# mission_unsleepable.net
KiCad netlist of a schematic drawn in Altium Designer
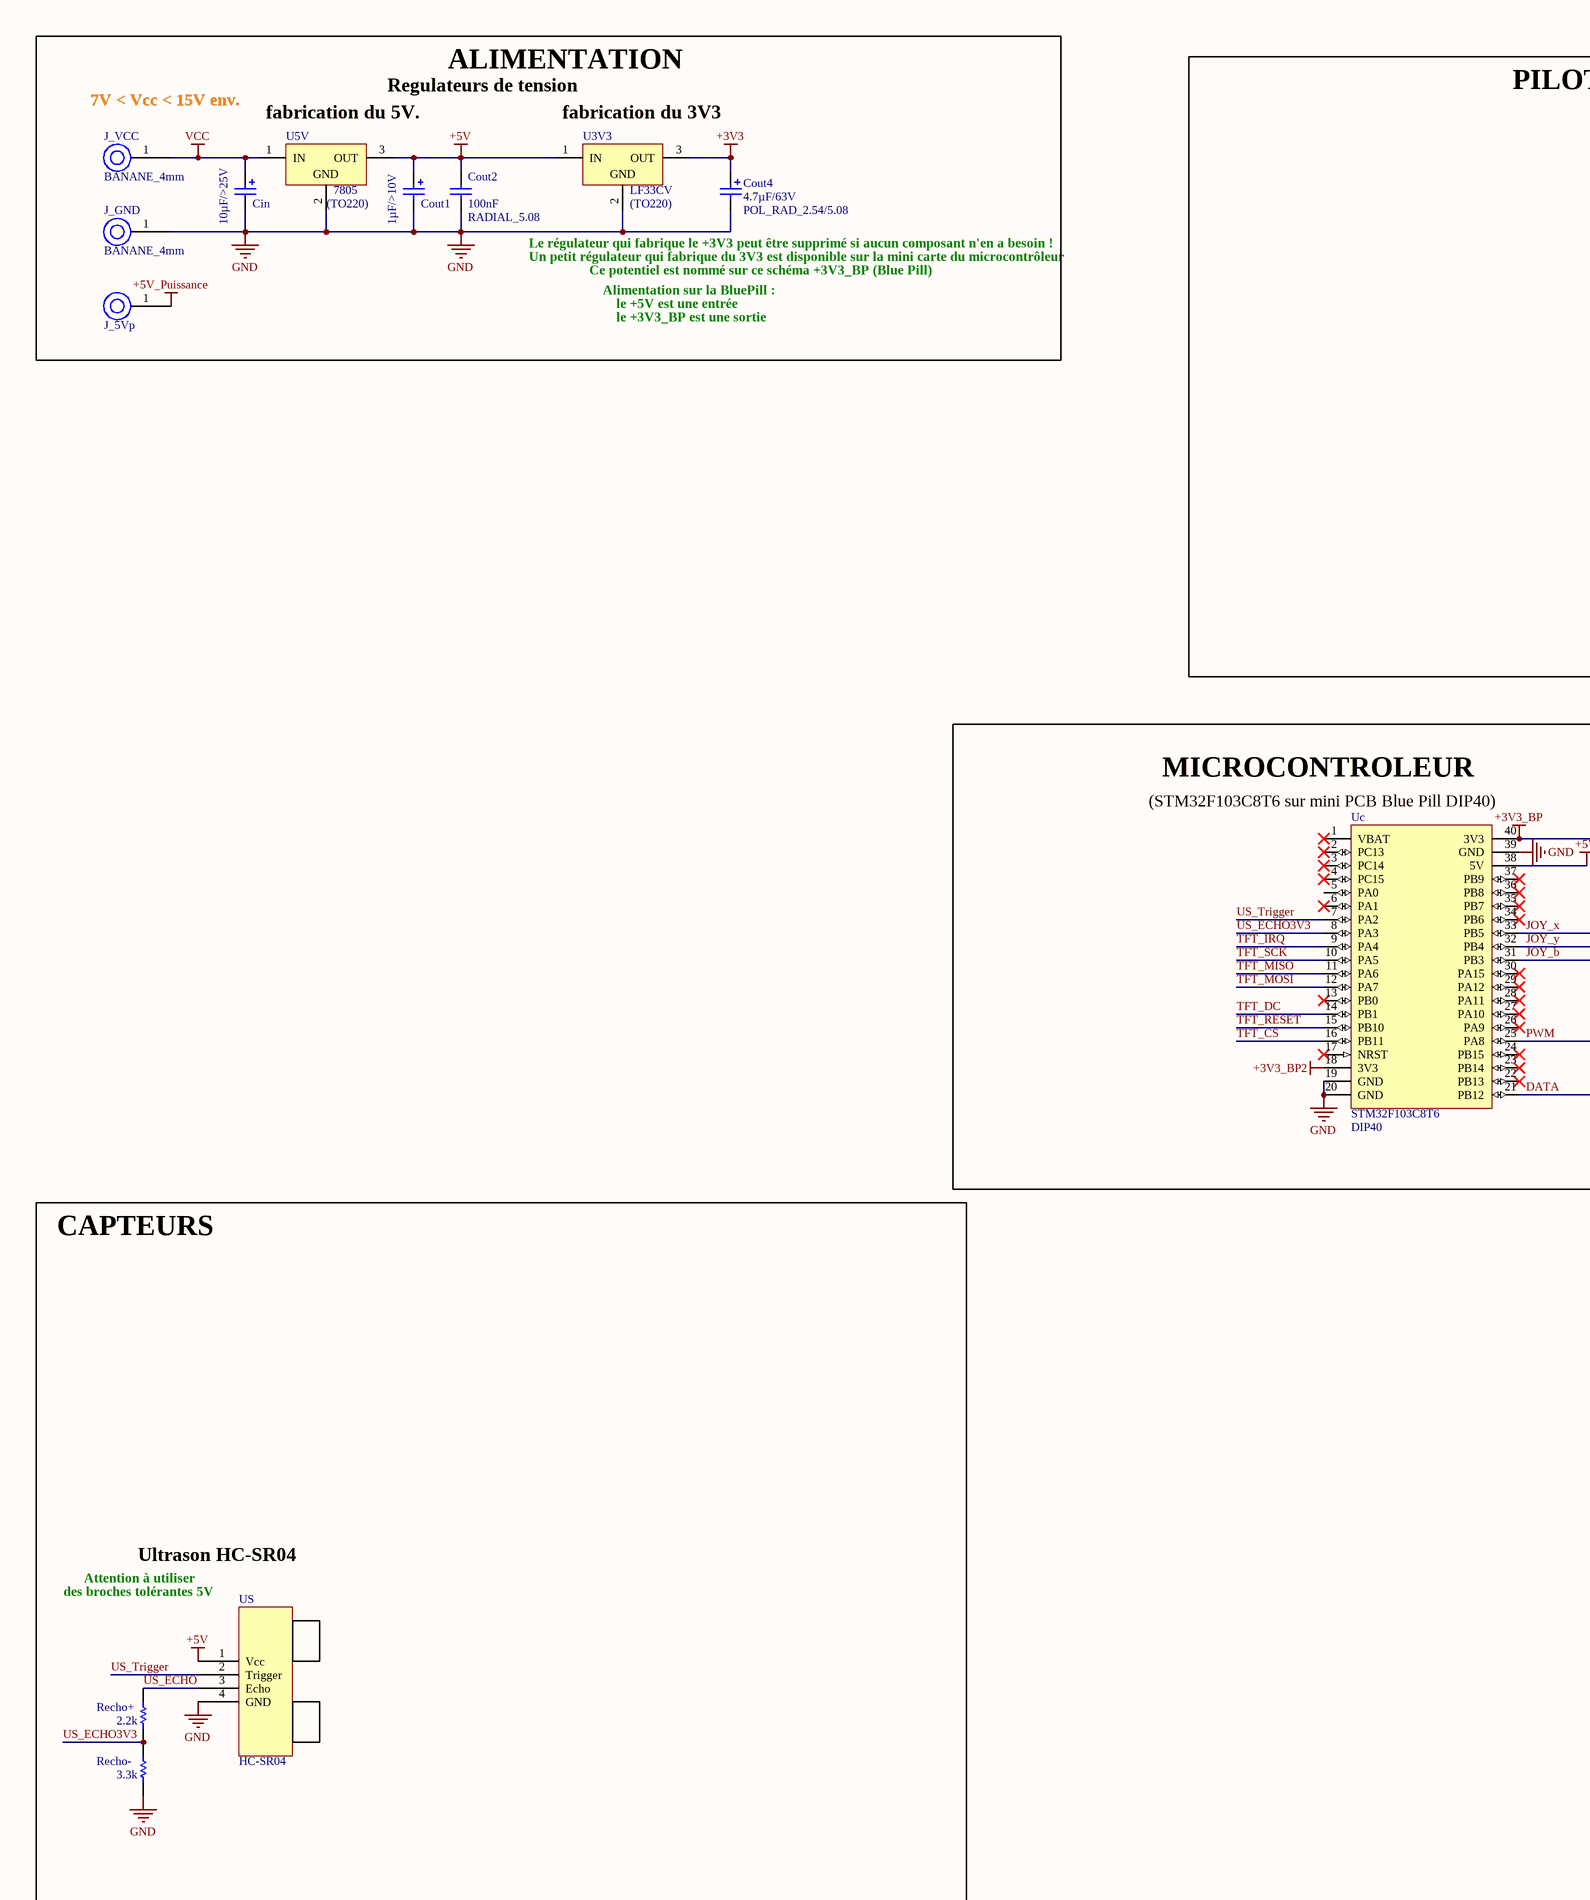
[diagram p0: mission_unsleepable.SchDoc, left]
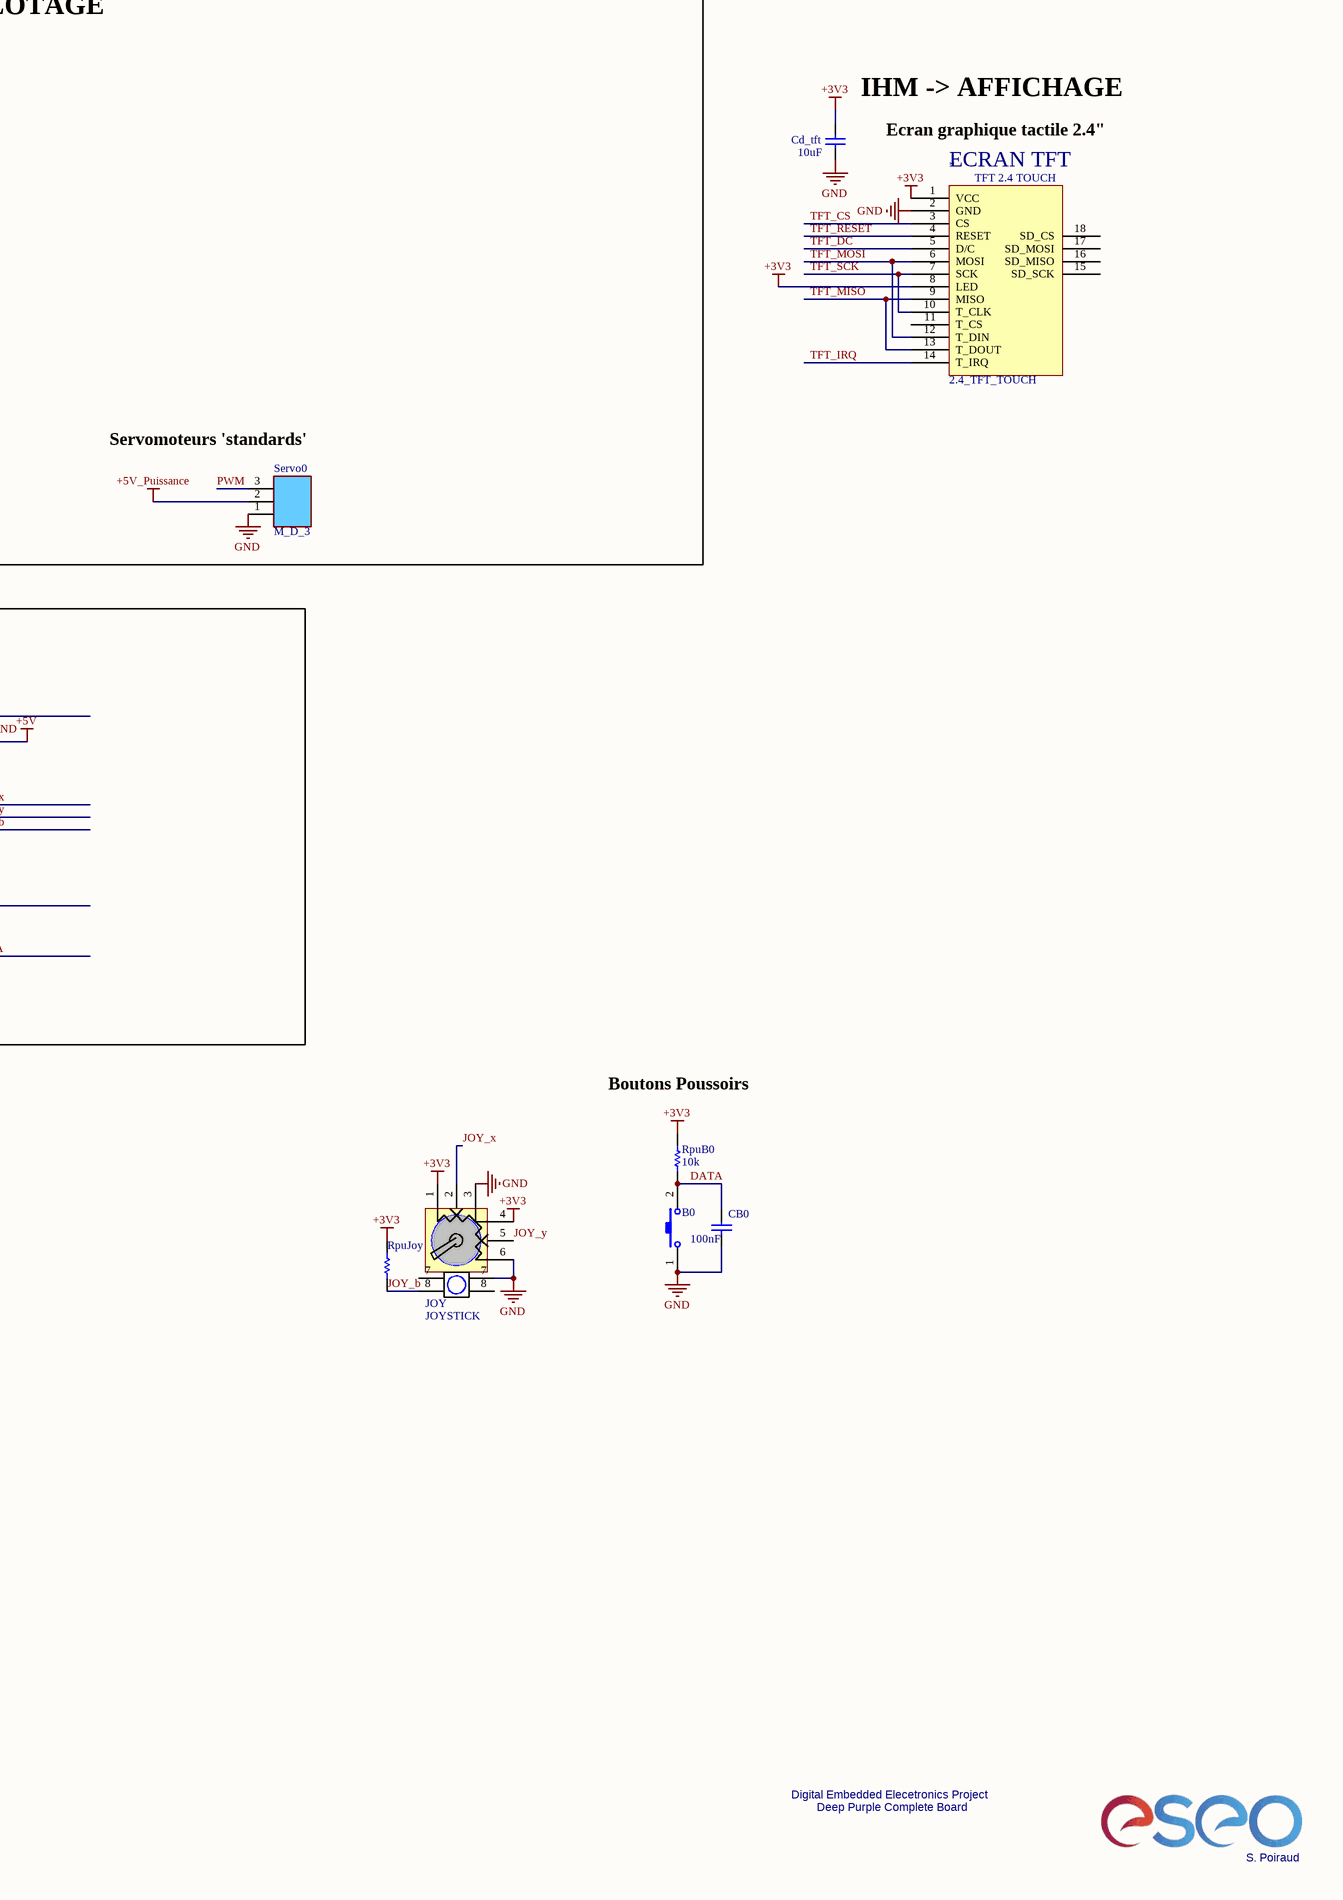
[diagram p1: mission_unsleepable.SchDoc, right]

(export (version "E")
  (design (tool "Eeschema 10.0.6"))
  (components
    (comp (ref "*")
      (value "2.4_TFT_TOUCH")
      (footprint "2.4_TFT_TOUCH")
      (libsource (lib "_ROBOT") (part "2.4_TFT_TOUCH"))
    )
    (comp (ref "B0")
      (value "BOUTON_POUSSOIR_MINIATURE_TRAVERSANT")
      (footprint "BOUTON_POUSSE_PLAT_6x6")
      (description "BOUTON POUSSOIR MINIATURE TRAVERSANT ON/OFF")
      (libsource (lib "commutation") (part "BOUTON_POUSSOIR_MINIATURE_TRAVERSANT"))
    )
    (comp (ref "CB0")
      (value "100nF")
      (footprint "C0805_N")
      (fields (field (name "Comment") "Condensateur 0805"))
      (libsource (lib "composants passifs") (part "CONDENSATEUR_CER_RAD_5.08"))
    )
    (comp (ref "Cd_tft")
      (value "10uF")
      (footprint "CONDENSATEUR_POLARISE_ELECTROLYTIQUE_RADIAL_2.54/5.08")
      (description "Capacitor")
      (fields (field (name "PUBLISHER") "Altium Limited"))
      (libsource (lib "_ROBOT") (part "Condensateur"))
    )
    (comp (ref "Cin")
      (value "10µF/>25V")
      (footprint "CONDENSATEUR_POLARISE_ELECTROLYTIQUE_RADIAL_2.0/5.08")
      (description "CONDENSATEUR POLARISE ELECTROLYTIQUE RADIAL 2.0/5.08")
      (fields (field (name "Comment") "CONDENSATEUR_POL_ELECTROLY_RAD_2.0/5.08"))
      (libsource (lib "composants passifs") (part "CONDENSATEUR_POL_ELECTROLY_RAD_2.0/5.08"))
    )
    (comp (ref "Cout1")
      (value "1µF/>10V")
      (footprint "CONDENSATEUR_POLARISE_ELECTROLYTIQUE_RADIAL_2.0/5.08")
      (description "CONDENSATEUR POLARISE ELECTROLYTIQUE RADIAL 2.0/5.08")
      (fields (field (name "Comment") "CONDENSATEUR_POL_ELECTROLY_RAD_2.0/5.08"))
      (libsource (lib "composants passifs") (part "CONDENSATEUR_POL_ELECTROLY_RAD_2.0/5.08"))
    )
    (comp (ref "Cout2")
      (value "100nF")
      (footprint "CONDENSATEUR_CERAMIQUE_RADIAL_5.08")
      (description "CONDENSATEUR TRAVERSANT CERAMIQUE RADIAL 5.08mm")
      (fields (field (name "TYPE") "RADIAL_5.08") (field (name "Comment") "CONDENSATEUR_CER_RAD_5.08"))
      (libsource (lib "composants passifs") (part "CONDENSATEUR_CER_RAD_5.08"))
    )
    (comp (ref "Cout4")
      (value "4.7µF/63V")
      (footprint "CONDENSATEUR_POLARISE_ELECTROLYTIQUE_RADIAL_2.54/5.08")
      (description "CONDENSATEUR POLARISE ELECTROLYTIQUE RADIAL 2.54/5.08")
      (fields
        (field (name "TYPE") "POL_RAD_2.54/5.08")
        (field (name "Comment") "CONDENSATEUR_POL_ELECTROLY_RAD_2.54/5.08")
      )
      (libsource (lib "composants passifs") (part "CONDENSATEUR_POL_ELECTROLY_RAD_2.54/5.08"))
    )
    (comp (ref "JOY")
      (value "JOYSTICK_MINI_AVEC_SWITCH")
      (footprint "JOYSTICK_MINI - avec Switch")
      (description "JOYSTICK POTENTIOMETRIQUE MINIATURE RKJXK122000D")
      (fields (field (name "TYPE") "JOYSTICK"))
      (libsource (lib "electromecanique") (part "JOYSTICK_MINI_AVEC_SWITCH"))
    )
    (comp (ref "J_5Vp")
      (value "DOUILLE BANANE 4mm")
      (footprint "DOUILLE_BANANE_4mm")
      (description "DOUILLE BANANE 4 mm")
      (libsource (lib "connecteurs") (part "DOUILLE_BANANE_4mm"))
    )
    (comp (ref "J_GND")
      (value "DOUILLE BANANE 4mm")
      (footprint "DOUILLE_BANANE_4mm")
      (description "DOUILLE BANANE 4 mm")
      (fields (field (name "TYPE") "BANANE_4mm"))
      (libsource (lib "connecteurs") (part "DOUILLE_BANANE_4mm"))
    )
    (comp (ref "J_VCC")
      (value "DOUILLE BANANE 4mm")
      (footprint "DOUILLE_BANANE_4mm")
      (description "DOUILLE BANANE 4 mm")
      (fields (field (name "TYPE") "BANANE_4mm"))
      (libsource (lib "connecteurs") (part "DOUILLE_BANANE_4mm"))
    )
    (comp (ref "Recho+")
      (value "2.2k")
      (footprint "R1206_N")
      (description "Resistor")
      (fields (field (name "PUBLISHER") "Altium Limited"))
      (libsource (lib "_ROBOT") (part "Resistor"))
    )
    (comp (ref "Recho-")
      (value "3.3k")
      (footprint "R1206_N")
      (description "Resistor")
      (fields (field (name "PUBLISHER") "Altium Limited"))
      (libsource (lib "_ROBOT") (part "Resistor"))
    )
    (comp (ref "RpuB0")
      (value "10k")
      (footprint "RESISTANCE_CMS_1206")
      (description "RESISTANCE CMS 1206")
      (fields (field (name "Comment") "RESISTANCE_CMS_1206"))
      (libsource (lib "composants passifs") (part "RESISTANCE_CMS_1206"))
    )
    (comp (ref "RpuJoy")
      (value "RESISTANCE_CMS_1206")
      (footprint "RESISTANCE_CMS_1206")
      (description "RESISTANCE CMS 1206")
      (libsource (lib "composants passifs") (part "RESISTANCE_CMS_1206"))
    )
    (comp (ref "Servo0")
      (value "BARRETTE 3 CONTACTS 1 RANGEE MALE DROITE")
      (footprint "BARRETTE_3_M_D")
      (fields (field (name "TYPE") "M_D_3"))
      (libsource (lib "connecteurs") (part "BARRETTE_3 CONTACTS_1 RANGEE_MALE_DROITE"))
    )
    (comp (ref "U3V3")
      (value "REGULATEUR_TO220_78XX")
      (footprint "REGULATEUR_TO220_78XX")
      (description "REGULATEUR DE TENSION POSITIVE 78XX BOITIER TO220")
      (fields (field (name "TYPE") "LF33CV") (field (name "PACKAGE") "(TO220)"))
      (libsource (lib "composants actifs") (part "REGULATEUR_TO220_78XX"))
    )
    (comp (ref "U5V")
      (value "REGULATEUR_TO220_78XX")
      (footprint "REGULATEUR_TO220_78XX")
      (description "REGULATEUR DE TENSION POSITIVE 78XX BOITIER TO220")
      (fields (field (name "TYPE") "7805") (field (name "PACKAGE") "(TO220)"))
      (libsource (lib "composants actifs") (part "REGULATEUR_TO220_78XX"))
    )
    (comp (ref "Uc")
      (value "STM32F103C8T6/PCB_DIP40")
      (footprint "STM32F103C8T6_DIP40")
      (fields (field (name "TYPE") "STM32F103C8T6") (field (name "PACKAGE") "DIP40"))
      (libsource (lib "circuits integres") (part "STM32F103C8T6/PCB_DIP40"))
    )
    (comp (ref "US") (value "HC-SR04") (footprint "HC-SR04") (libsource (lib "DEEP") (part "HC-SR04")))
  )
  (nets
    (net (code "1") (name "+3V3") (class "Default")
      (node (ref "*") (pin "1") (pinfunction "VCC_1") (pintype "passive"))
      (node (ref "*") (pin "8") (pinfunction "LED_8") (pintype "passive"))
      (node (ref "Cd_tft") (pin "1") (pinfunction "1_1") (pintype "passive"))
      (node (ref "Cout4") (pin "1") (pinfunction "1_1") (pintype "passive"))
      (node (ref "JOY") (pin "1") (pintype "passive"))
      (node (ref "JOY") (pin "4") (pintype "passive"))
      (node (ref "RpuB0") (pin "2") (pinfunction "2_2") (pintype "passive"))
      (node (ref "RpuJoy") (pin "2") (pinfunction "2_2") (pintype "passive"))
      (node (ref "U3V3") (pin "3") (pinfunction "OUT_3") (pintype "power_in"))
    )
    (net (code "2") (name "+3V3_BP") (class "Default")
      (node (ref "Uc") (pin "40") (pinfunction "3V3_40") (pintype "power_in"))
    )
    (net (code "3") (name "+3V3_BP2") (class "Default")
      (node (ref "Uc") (pin "18") (pinfunction "3V3_18") (pintype "power_in"))
    )
    (net (code "4") (name "+5V") (class "Default")
      (node (ref "Cout1") (pin "1") (pinfunction "1_1") (pintype "passive"))
      (node (ref "Cout2") (pin "2") (pinfunction "2_2") (pintype "passive"))
      (node (ref "U3V3") (pin "1") (pinfunction "IN_1") (pintype "power_in"))
      (node (ref "U5V") (pin "3") (pinfunction "OUT_3") (pintype "power_in"))
      (node (ref "US") (pin "1") (pinfunction "Vcc_1") (pintype "passive"))
      (node (ref "Uc") (pin "38") (pinfunction "5V_38") (pintype "power_in"))
    )
    (net (code "5") (name "+5V_Puissance") (class "Default")
      (node (ref "J_5Vp") (pin "1") (pinfunction "1_1") (pintype "passive"))
      (node (ref "Servo0") (pin "2") (pinfunction "2_2") (pintype "passive"))
    )
    (net (code "6") (name "/DATA") (class "Default")
      (node (ref "B0") (pin "2") (pinfunction "2_2") (pintype "passive"))
      (node (ref "CB0") (pin "2") (pinfunction "2_2") (pintype "passive"))
      (node (ref "RpuB0") (pin "1") (pinfunction "1_1") (pintype "passive"))
      (node (ref "Uc") (pin "21") (pinfunction "PB12_21") (pintype "bidirectional"))
    )
    (net (code "7") (name "/JOY_b") (class "Default")
      (node (ref "JOY") (pin "8") (pintype "passive"))
      (node (ref "RpuJoy") (pin "1") (pinfunction "1_1") (pintype "passive"))
      (node (ref "Uc") (pin "31") (pinfunction "PB3_31") (pintype "bidirectional"))
    )
    (net (code "8") (name "/JOY_x") (class "Default")
      (node (ref "JOY") (pin "2") (pintype "passive"))
      (node (ref "Uc") (pin "33") (pinfunction "PB5_33") (pintype "bidirectional"))
    )
    (net (code "9") (name "/JOY_y") (class "Default")
      (node (ref "JOY") (pin "5") (pintype "passive"))
      (node (ref "Uc") (pin "32") (pinfunction "PB4_32") (pintype "bidirectional"))
    )
    (net (code "10") (name "/PWM") (class "Default")
      (node (ref "Servo0") (pin "3") (pinfunction "3_3") (pintype "passive"))
      (node (ref "Uc") (pin "25") (pinfunction "PA8_25") (pintype "bidirectional"))
    )
    (net (code "11") (name "/TFT_CS") (class "Default")
      (node (ref "*") (pin "3") (pinfunction "CS_3") (pintype "passive"))
      (node (ref "Uc") (pin "16") (pinfunction "PB11_16") (pintype "bidirectional"))
    )
    (net (code "12") (name "/TFT_DC") (class "Default")
      (node (ref "*") (pin "5") (pinfunction "D/C_5") (pintype "passive"))
      (node (ref "Uc") (pin "14") (pinfunction "PB1_14") (pintype "bidirectional"))
    )
    (net (code "13") (name "/TFT_IRQ") (class "Default")
      (node (ref "*") (pin "14") (pinfunction "T_IRQ_14") (pintype "passive"))
      (node (ref "Uc") (pin "9") (pinfunction "PA4_9") (pintype "bidirectional"))
    )
    (net (code "14") (name "/TFT_MISO") (class "Default")
      (node (ref "*") (pin "13") (pinfunction "T_DOUT_13") (pintype "passive"))
      (node (ref "*") (pin "9") (pinfunction "MISO_9") (pintype "passive"))
      (node (ref "Uc") (pin "11") (pinfunction "PA6_11") (pintype "bidirectional"))
    )
    (net (code "15") (name "/TFT_MOSI") (class "Default")
      (node (ref "*") (pin "12") (pinfunction "T_DIN_12") (pintype "passive"))
      (node (ref "*") (pin "6") (pinfunction "MOSI_6") (pintype "passive"))
      (node (ref "Uc") (pin "12") (pinfunction "PA7_12") (pintype "bidirectional"))
    )
    (net (code "16") (name "/TFT_RESET") (class "Default")
      (node (ref "*") (pin "4") (pinfunction "RESET_4") (pintype "passive"))
      (node (ref "Uc") (pin "15") (pinfunction "PB10_15") (pintype "bidirectional"))
    )
    (net (code "17") (name "/TFT_SCK") (class "Default")
      (node (ref "*") (pin "10") (pinfunction "T_CLK_10") (pintype "passive"))
      (node (ref "*") (pin "7") (pinfunction "SCK_7") (pintype "passive"))
      (node (ref "Uc") (pin "10") (pinfunction "PA5_10") (pintype "bidirectional"))
    )
    (net (code "18") (name "/US_ECHO") (class "Default")
      (node (ref "Recho+") (pin "2") (pinfunction "2_2") (pintype "passive"))
      (node (ref "US") (pin "3") (pinfunction "Echo_3") (pintype "passive"))
    )
    (net (code "19") (name "/US_ECHO3V3") (class "Default")
      (node (ref "Recho+") (pin "1") (pinfunction "1_1") (pintype "passive"))
      (node (ref "Recho-") (pin "2") (pinfunction "2_2") (pintype "passive"))
      (node (ref "Uc") (pin "8") (pinfunction "PA3_8") (pintype "bidirectional"))
    )
    (net (code "20") (name "/US_Trigger") (class "Default")
      (node (ref "US") (pin "2") (pinfunction "Trigger_2") (pintype "passive"))
      (node (ref "Uc") (pin "7") (pinfunction "PA2_7") (pintype "bidirectional"))
    )
    (net (code "21") (name "GND") (class "Default")
      (node (ref "*") (pin "2") (pinfunction "GND_2") (pintype "passive"))
      (node (ref "B0") (pin "1") (pinfunction "1_1") (pintype "passive"))
      (node (ref "CB0") (pin "1") (pinfunction "1_1") (pintype "passive"))
      (node (ref "Cd_tft") (pin "2") (pinfunction "2_2") (pintype "passive"))
      (node (ref "Cin") (pin "2") (pinfunction "2_2") (pintype "passive"))
      (node (ref "Cout1") (pin "2") (pinfunction "2_2") (pintype "passive"))
      (node (ref "Cout2") (pin "1") (pinfunction "1_1") (pintype "passive"))
      (node (ref "Cout4") (pin "2") (pinfunction "2_2") (pintype "passive"))
      (node (ref "JOY") (pin "3") (pintype "passive"))
      (node (ref "JOY") (pin "6") (pintype "passive"))
      (node (ref "JOY") (pin "7") (pintype "passive"))
      (node (ref "J_GND") (pin "1") (pinfunction "1_1") (pintype "passive"))
      (node (ref "Recho-") (pin "1") (pinfunction "1_1") (pintype "passive"))
      (node (ref "Servo0") (pin "1") (pinfunction "1_1") (pintype "passive"))
      (node (ref "U3V3") (pin "2") (pinfunction "GND_2") (pintype "power_in"))
      (node (ref "U5V") (pin "2") (pinfunction "GND_2") (pintype "power_in"))
      (node (ref "US") (pin "4") (pinfunction "GND_4") (pintype "passive"))
      (node (ref "Uc") (pin "19") (pinfunction "GND_19") (pintype "power_in"))
      (node (ref "Uc") (pin "20") (pinfunction "GND_20") (pintype "power_in"))
      (node (ref "Uc") (pin "39") (pinfunction "GND_39") (pintype "power_in"))
    )
    (net (code "22") (name "VCC") (class "Default")
      (node (ref "Cin") (pin "1") (pinfunction "1_1") (pintype "passive"))
      (node (ref "J_VCC") (pin "1") (pinfunction "1_1") (pintype "passive"))
      (node (ref "U5V") (pin "1") (pinfunction "IN_1") (pintype "power_in"))
    )
    (net (code "23") (name "unconnected-(*-SD_CS-Pad18)") (class "Default")
      (node (ref "*") (pin "18") (pinfunction "SD_CS_18") (pintype "passive"))
    )
    (net (code "24") (name "unconnected-(*-SD_MISO-Pad16)") (class "Default")
      (node (ref "*") (pin "16") (pinfunction "SD_MISO_16") (pintype "passive"))
    )
    (net (code "25") (name "unconnected-(*-SD_MOSI-Pad17)") (class "Default")
      (node (ref "*") (pin "17") (pinfunction "SD_MOSI_17") (pintype "passive"))
    )
    (net (code "26") (name "unconnected-(*-SD_SCK-Pad15)") (class "Default")
      (node (ref "*") (pin "15") (pinfunction "SD_SCK_15") (pintype "passive"))
    )
    (net (code "27") (name "unconnected-(*-T_CS-Pad11)") (class "Default")
      (node (ref "*") (pin "11") (pinfunction "T_CS_11") (pintype "passive"))
    )
    (net (code "28") (name "unconnected-(JOY-Pad7)") (class "Default")
      (node (ref "JOY") (pin "7") (pintype "passive"))
    )
    (net (code "29") (name "unconnected-(JOY-Pad8)") (class "Default")
      (node (ref "JOY") (pin "8") (pintype "passive"))
    )
    (net (code "30") (name "unconnected-(Uc-NRST-Pad17)") (class "Default")
      (node (ref "Uc") (pin "17") (pinfunction "NRST_17") (pintype "input+no_connect"))
    )
    (net (code "31") (name "unconnected-(Uc-PA0-Pad5)") (class "Default")
      (node (ref "Uc") (pin "5") (pinfunction "PA0_5") (pintype "bidirectional"))
    )
    (net (code "32") (name "unconnected-(Uc-PA1-Pad6)") (class "Default")
      (node (ref "Uc") (pin "6") (pinfunction "PA1_6") (pintype "bidirectional+no_connect"))
    )
    (net (code "33") (name "unconnected-(Uc-PA9-Pad26)") (class "Default")
      (node (ref "Uc") (pin "26") (pinfunction "PA9_26") (pintype "bidirectional+no_connect"))
    )
    (net (code "34") (name "unconnected-(Uc-PA10-Pad27)") (class "Default")
      (node (ref "Uc") (pin "27") (pinfunction "PA10_27") (pintype "bidirectional+no_connect"))
    )
    (net (code "35") (name "unconnected-(Uc-PA11-Pad28)") (class "Default")
      (node (ref "Uc") (pin "28") (pinfunction "PA11_28") (pintype "bidirectional+no_connect"))
    )
    (net (code "36") (name "unconnected-(Uc-PA12-Pad29)") (class "Default")
      (node (ref "Uc") (pin "29") (pinfunction "PA12_29") (pintype "bidirectional+no_connect"))
    )
    (net (code "37") (name "unconnected-(Uc-PA15-Pad30)") (class "Default")
      (node (ref "Uc") (pin "30") (pinfunction "PA15_30") (pintype "bidirectional+no_connect"))
    )
    (net (code "38") (name "unconnected-(Uc-PB0-Pad13)") (class "Default")
      (node (ref "Uc") (pin "13") (pinfunction "PB0_13") (pintype "bidirectional+no_connect"))
    )
    (net (code "39") (name "unconnected-(Uc-PB6-Pad34)") (class "Default")
      (node (ref "Uc") (pin "34") (pinfunction "PB6_34") (pintype "bidirectional+no_connect"))
    )
    (net (code "40") (name "unconnected-(Uc-PB7-Pad35)") (class "Default")
      (node (ref "Uc") (pin "35") (pinfunction "PB7_35") (pintype "bidirectional+no_connect"))
    )
    (net (code "41") (name "unconnected-(Uc-PB8-Pad36)") (class "Default")
      (node (ref "Uc") (pin "36") (pinfunction "PB8_36") (pintype "bidirectional+no_connect"))
    )
    (net (code "42") (name "unconnected-(Uc-PB9-Pad37)") (class "Default")
      (node (ref "Uc") (pin "37") (pinfunction "PB9_37") (pintype "bidirectional+no_connect"))
    )
    (net (code "43") (name "unconnected-(Uc-PB13-Pad22)") (class "Default")
      (node (ref "Uc") (pin "22") (pinfunction "PB13_22") (pintype "bidirectional+no_connect"))
    )
    (net (code "44") (name "unconnected-(Uc-PB14-Pad23)") (class "Default")
      (node (ref "Uc") (pin "23") (pinfunction "PB14_23") (pintype "bidirectional+no_connect"))
    )
    (net (code "45") (name "unconnected-(Uc-PB15-Pad24)") (class "Default")
      (node (ref "Uc") (pin "24") (pinfunction "PB15_24") (pintype "bidirectional+no_connect"))
    )
    (net (code "46") (name "unconnected-(Uc-PC13-Pad2)") (class "Default")
      (node (ref "Uc") (pin "2") (pinfunction "PC13_2") (pintype "bidirectional+no_connect"))
    )
    (net (code "47") (name "unconnected-(Uc-PC14-Pad3)") (class "Default")
      (node (ref "Uc") (pin "3") (pinfunction "PC14_3") (pintype "bidirectional+no_connect"))
    )
    (net (code "48") (name "unconnected-(Uc-PC15-Pad4)") (class "Default")
      (node (ref "Uc") (pin "4") (pinfunction "PC15_4") (pintype "bidirectional+no_connect"))
    )
    (net (code "49") (name "unconnected-(Uc-VBAT-Pad1)") (class "Default")
      (node (ref "Uc") (pin "1") (pinfunction "VBAT_1") (pintype "power_in+no_connect"))
    )
  )
)
